# Atmega32_Dev.net
KiCad netlist of a schematic drawn in EAGLE
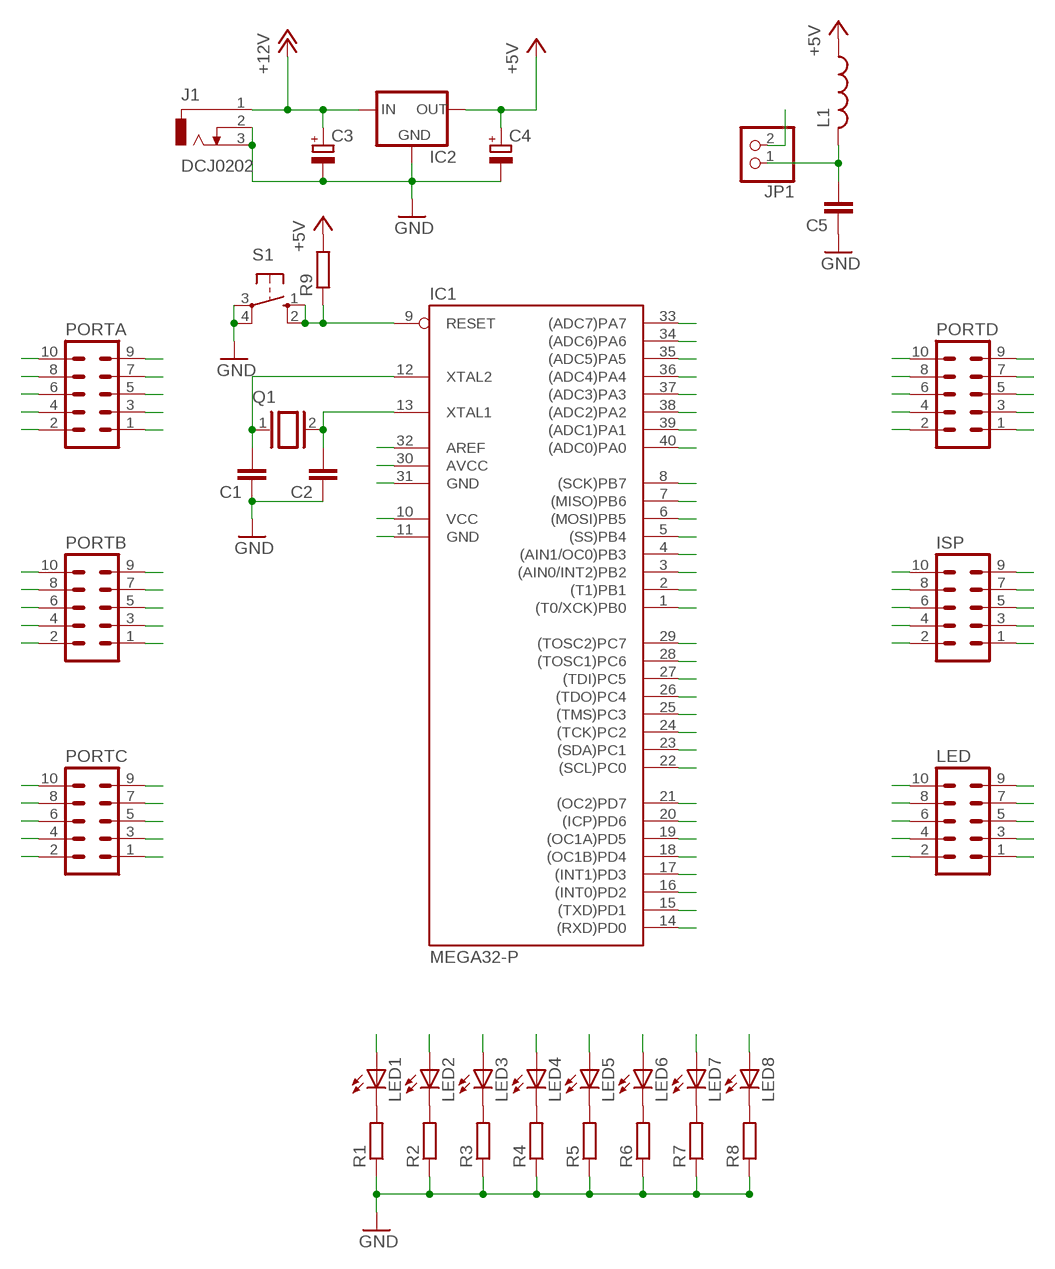
[diagram p0: schematic, sheet 1]

(export (version "E")
  (design (tool "Eeschema 10.0.6"))
  (components
    (comp (ref "C1")
      (value "CAP1206")
      (footprint "eagle-import:1206")
      (libsource (lib "eagle-import") (part "CAP1206"))
    )
    (comp (ref "C2")
      (value "CAP1206")
      (footprint "eagle-import:1206")
      (libsource (lib "eagle-import") (part "CAP1206"))
    )
    (comp (ref "C3")
      (value "CPOL-EUE5-6")
      (footprint "eagle-import:E5-6")
      (libsource (lib "eagle-import") (part "CPOL-EUE5-6"))
    )
    (comp (ref "C4")
      (value "CPOL-EUE5-6")
      (footprint "eagle-import:E5-6")
      (libsource (lib "eagle-import") (part "CPOL-EUE5-6"))
    )
    (comp (ref "C5")
      (value "CAP1206")
      (footprint "eagle-import:1206")
      (libsource (lib "eagle-import") (part "CAP1206"))
    )
    (comp (ref "IC1")
      (value "MEGA32-P")
      (footprint "eagle-import:DIL40")
      (fields (field (name "MPN") "ATMEGA32-16PU"))
      (libsource (lib "eagle-import") (part "MEGA32-P"))
    )
    (comp (ref "IC2")
      (value "78XXL")
      (footprint "eagle-import:78XXL")
      (libsource (lib "eagle-import") (part "78XXL"))
    )
    (comp (ref "ISP")
      (value "ML10")
      (footprint "eagle-import:ML10")
      (libsource (lib "eagle-import") (part "ML10"))
    )
    (comp (ref "J1")
      (value "DCJ0202")
      (footprint "eagle-import:DCJ0202")
      (libsource (lib "eagle-import") (part "DCJ0202"))
    )
    (comp (ref "JP1")
      (value "PINHD-1X2")
      (footprint "eagle-import:1X02")
      (libsource (lib "eagle-import") (part "PINHD-1X2"))
    )
    (comp (ref "L1")
      (value "L-US0204/5")
      (footprint "eagle-import:0204_5")
      (libsource (lib "eagle-import") (part "L-US0204/5"))
    )
    (comp (ref "LED")
      (value "ML10")
      (footprint "eagle-import:ML10")
      (libsource (lib "eagle-import") (part "ML10"))
    )
    (comp (ref "LED1")
      (value "LED3MM")
      (footprint "eagle-import:LED3MM")
      (libsource (lib "eagle-import") (part "LED3MM"))
    )
    (comp (ref "LED2")
      (value "LED3MM")
      (footprint "eagle-import:LED3MM")
      (libsource (lib "eagle-import") (part "LED3MM"))
    )
    (comp (ref "LED3")
      (value "LED3MM")
      (footprint "eagle-import:LED3MM")
      (libsource (lib "eagle-import") (part "LED3MM"))
    )
    (comp (ref "LED4")
      (value "LED3MM")
      (footprint "eagle-import:LED3MM")
      (libsource (lib "eagle-import") (part "LED3MM"))
    )
    (comp (ref "LED5")
      (value "LED3MM")
      (footprint "eagle-import:LED3MM")
      (libsource (lib "eagle-import") (part "LED3MM"))
    )
    (comp (ref "LED6")
      (value "LED3MM")
      (footprint "eagle-import:LED3MM")
      (libsource (lib "eagle-import") (part "LED3MM"))
    )
    (comp (ref "LED7")
      (value "LED3MM")
      (footprint "eagle-import:LED3MM")
      (libsource (lib "eagle-import") (part "LED3MM"))
    )
    (comp (ref "LED8")
      (value "LED3MM")
      (footprint "eagle-import:LED3MM")
      (libsource (lib "eagle-import") (part "LED3MM"))
    )
    (comp (ref "PORTA")
      (value "ML10")
      (footprint "eagle-import:ML10")
      (libsource (lib "eagle-import") (part "ML10"))
    )
    (comp (ref "PORTB")
      (value "ML10")
      (footprint "eagle-import:ML10")
      (libsource (lib "eagle-import") (part "ML10"))
    )
    (comp (ref "PORTC")
      (value "ML10")
      (footprint "eagle-import:ML10")
      (libsource (lib "eagle-import") (part "ML10"))
    )
    (comp (ref "PORTD")
      (value "ML10")
      (footprint "eagle-import:ML10")
      (libsource (lib "eagle-import") (part "ML10"))
    )
    (comp (ref "Q1")
      (value "XTAL/S")
      (footprint "eagle-import:QS")
      (libsource (lib "eagle-import") (part "XTAL/S"))
    )
    (comp (ref "R1")
      (value "R-EU_M1206")
      (footprint "eagle-import:M1206")
      (libsource (lib "eagle-import") (part "resistor_R-EU_M1206"))
    )
    (comp (ref "R2")
      (value "R-EU_M1206")
      (footprint "eagle-import:M1206")
      (libsource (lib "eagle-import") (part "resistor_R-EU_M1206"))
    )
    (comp (ref "R3")
      (value "R-EU_M1206")
      (footprint "eagle-import:M1206")
      (libsource (lib "eagle-import") (part "resistor_R-EU_M1206"))
    )
    (comp (ref "R4")
      (value "R-EU_M1206")
      (footprint "eagle-import:M1206")
      (libsource (lib "eagle-import") (part "resistor_R-EU_M1206"))
    )
    (comp (ref "R5")
      (value "R-EU_M1206")
      (footprint "eagle-import:M1206")
      (libsource (lib "eagle-import") (part "resistor_R-EU_M1206"))
    )
    (comp (ref "R6")
      (value "R-EU_M1206")
      (footprint "eagle-import:M1206")
      (libsource (lib "eagle-import") (part "resistor_R-EU_M1206"))
    )
    (comp (ref "R7")
      (value "R-EU_M1206")
      (footprint "eagle-import:M1206")
      (libsource (lib "eagle-import") (part "resistor_R-EU_M1206"))
    )
    (comp (ref "R8")
      (value "R-EU_M1206")
      (footprint "eagle-import:M1206")
      (libsource (lib "eagle-import") (part "resistor_R-EU_M1206"))
    )
    (comp (ref "R9")
      (value "R-EU_0204/7")
      (footprint "eagle-import:0204_7")
      (libsource (lib "eagle-import") (part "R-EU_0204/7"))
    )
    (comp (ref "S1")
      (value "10-XX")
      (footprint "eagle-import:B3F-10XX")
      (fields (field (name "MPN") "B3F-1000"))
      (libsource (lib "eagle-import") (part "10-XX"))
    )
  )
  (nets
    (net (code "1") (name "+5V") (class "Default")
      (node (ref "C4") (pin "+") (pinfunction "+_+") (pintype "passive"))
      (node (ref "IC1") (pin "10") (pinfunction "VCC_10") (pintype "power_in"))
      (node (ref "IC2") (pin "OUT") (pinfunction "OUT_OUT") (pintype "passive"))
      (node (ref "ISP") (pin "2") (pinfunction "2_2") (pintype "passive"))
      (node (ref "L1") (pin "1") (pinfunction "1_1") (pintype "passive"))
      (node (ref "LED") (pin "9") (pinfunction "9_9") (pintype "passive"))
      (node (ref "PORTA") (pin "9") (pinfunction "9_9") (pintype "passive"))
      (node (ref "PORTB") (pin "9") (pinfunction "9_9") (pintype "passive"))
      (node (ref "PORTC") (pin "9") (pinfunction "9_9") (pintype "passive"))
      (node (ref "PORTD") (pin "9") (pinfunction "9_9") (pintype "passive"))
      (node (ref "R9") (pin "2") (pinfunction "2_2") (pintype "passive"))
    )
    (net (code "2") (name "+12V") (class "Default")
      (node (ref "C3") (pin "+") (pinfunction "+_+") (pintype "passive"))
      (node (ref "IC2") (pin "IN") (pinfunction "IN_IN") (pintype "input"))
      (node (ref "J1") (pin "1") (pinfunction "1_1") (pintype "passive"))
    )
    (net (code "3") (name "/AREF") (class "Default")
      (node (ref "IC1") (pin "32") (pinfunction "AREF_32") (pintype "passive"))
      (node (ref "JP1") (pin "2") (pinfunction "2_2") (pintype "passive"))
    )
    (net (code "4") (name "/AVCC") (class "Default")
      (node (ref "C5") (pin "2") (pinfunction "2_2") (pintype "passive"))
      (node (ref "IC1") (pin "30") (pinfunction "AVCC_30") (pintype "power_in"))
      (node (ref "JP1") (pin "1") (pinfunction "1_1") (pintype "passive"))
      (node (ref "L1") (pin "2") (pinfunction "2_2") (pintype "passive"))
    )
    (net (code "5") (name "/L0") (class "Default")
      (node (ref "LED") (pin "1") (pinfunction "1_1") (pintype "passive"))
      (node (ref "LED1") (pin "A") (pinfunction "A_A") (pintype "passive"))
    )
    (net (code "6") (name "/L1") (class "Default")
      (node (ref "LED") (pin "2") (pinfunction "2_2") (pintype "passive"))
      (node (ref "LED2") (pin "A") (pinfunction "A_A") (pintype "passive"))
    )
    (net (code "7") (name "/L2") (class "Default")
      (node (ref "LED") (pin "3") (pinfunction "3_3") (pintype "passive"))
      (node (ref "LED3") (pin "A") (pinfunction "A_A") (pintype "passive"))
    )
    (net (code "8") (name "/L3") (class "Default")
      (node (ref "LED") (pin "4") (pinfunction "4_4") (pintype "passive"))
      (node (ref "LED4") (pin "A") (pinfunction "A_A") (pintype "passive"))
    )
    (net (code "9") (name "/L4") (class "Default")
      (node (ref "LED") (pin "5") (pinfunction "5_5") (pintype "passive"))
      (node (ref "LED5") (pin "A") (pinfunction "A_A") (pintype "passive"))
    )
    (net (code "10") (name "/L5") (class "Default")
      (node (ref "LED") (pin "6") (pinfunction "6_6") (pintype "passive"))
      (node (ref "LED6") (pin "A") (pinfunction "A_A") (pintype "passive"))
    )
    (net (code "11") (name "/L6") (class "Default")
      (node (ref "LED") (pin "7") (pinfunction "7_7") (pintype "passive"))
      (node (ref "LED7") (pin "A") (pinfunction "A_A") (pintype "passive"))
    )
    (net (code "12") (name "/L7") (class "Default")
      (node (ref "LED") (pin "8") (pinfunction "8_8") (pintype "passive"))
      (node (ref "LED8") (pin "A") (pinfunction "A_A") (pintype "passive"))
    )
    (net (code "13") (name "/PA0") (class "Default")
      (node (ref "IC1") (pin "40") (pinfunction "(ADC0)PA0_40") (pintype "bidirectional"))
      (node (ref "PORTA") (pin "1") (pinfunction "1_1") (pintype "passive"))
    )
    (net (code "14") (name "/PA1") (class "Default")
      (node (ref "IC1") (pin "39") (pinfunction "(ADC1)PA1_39") (pintype "bidirectional"))
      (node (ref "PORTA") (pin "2") (pinfunction "2_2") (pintype "passive"))
    )
    (net (code "15") (name "/PA2") (class "Default")
      (node (ref "IC1") (pin "38") (pinfunction "(ADC2)PA2_38") (pintype "bidirectional"))
      (node (ref "PORTA") (pin "3") (pinfunction "3_3") (pintype "passive"))
    )
    (net (code "16") (name "/PA3") (class "Default")
      (node (ref "IC1") (pin "37") (pinfunction "(ADC3)PA3_37") (pintype "bidirectional"))
      (node (ref "PORTA") (pin "4") (pinfunction "4_4") (pintype "passive"))
    )
    (net (code "17") (name "/PA4") (class "Default")
      (node (ref "IC1") (pin "36") (pinfunction "(ADC4)PA4_36") (pintype "bidirectional"))
      (node (ref "PORTA") (pin "5") (pinfunction "5_5") (pintype "passive"))
    )
    (net (code "18") (name "/PA5") (class "Default")
      (node (ref "IC1") (pin "35") (pinfunction "(ADC5)PA5_35") (pintype "bidirectional"))
      (node (ref "PORTA") (pin "6") (pinfunction "6_6") (pintype "passive"))
    )
    (net (code "19") (name "/PA6") (class "Default")
      (node (ref "IC1") (pin "34") (pinfunction "(ADC6)PA6_34") (pintype "bidirectional"))
      (node (ref "PORTA") (pin "7") (pinfunction "7_7") (pintype "passive"))
    )
    (net (code "20") (name "/PA7") (class "Default")
      (node (ref "IC1") (pin "33") (pinfunction "(ADC7)PA7_33") (pintype "bidirectional"))
      (node (ref "PORTA") (pin "8") (pinfunction "8_8") (pintype "passive"))
    )
    (net (code "21") (name "/PB0") (class "Default")
      (node (ref "IC1") (pin "1") (pinfunction "(T0/XCK)PB0_1") (pintype "bidirectional"))
      (node (ref "PORTB") (pin "1") (pinfunction "1_1") (pintype "passive"))
    )
    (net (code "22") (name "/PB1") (class "Default")
      (node (ref "IC1") (pin "2") (pinfunction "(T1)PB1_2") (pintype "bidirectional"))
      (node (ref "PORTB") (pin "2") (pinfunction "2_2") (pintype "passive"))
    )
    (net (code "23") (name "/PB2") (class "Default")
      (node (ref "IC1") (pin "3") (pinfunction "(AIN0/INT2)PB2_3") (pintype "bidirectional"))
      (node (ref "PORTB") (pin "3") (pinfunction "3_3") (pintype "passive"))
    )
    (net (code "24") (name "/PB3") (class "Default")
      (node (ref "IC1") (pin "4") (pinfunction "(AIN1/OC0)PB3_4") (pintype "bidirectional"))
      (node (ref "PORTB") (pin "4") (pinfunction "4_4") (pintype "passive"))
    )
    (net (code "25") (name "/PB4") (class "Default")
      (node (ref "IC1") (pin "5") (pinfunction "(SS)PB4_5") (pintype "bidirectional"))
      (node (ref "PORTB") (pin "5") (pinfunction "5_5") (pintype "passive"))
    )
    (net (code "26") (name "/PB5") (class "Default")
      (node (ref "IC1") (pin "6") (pinfunction "(MOSI)PB5_6") (pintype "bidirectional"))
      (node (ref "ISP") (pin "9") (pinfunction "9_9") (pintype "passive"))
      (node (ref "PORTB") (pin "6") (pinfunction "6_6") (pintype "passive"))
    )
    (net (code "27") (name "/PB6") (class "Default")
      (node (ref "IC1") (pin "7") (pinfunction "(MISO)PB6_7") (pintype "bidirectional"))
      (node (ref "ISP") (pin "1") (pinfunction "1_1") (pintype "passive"))
      (node (ref "PORTB") (pin "7") (pinfunction "7_7") (pintype "passive"))
    )
    (net (code "28") (name "/PB7") (class "Default")
      (node (ref "IC1") (pin "8") (pinfunction "(SCK)PB7_8") (pintype "bidirectional"))
      (node (ref "ISP") (pin "7") (pinfunction "7_7") (pintype "passive"))
      (node (ref "PORTB") (pin "8") (pinfunction "8_8") (pintype "passive"))
    )
    (net (code "29") (name "/PC0") (class "Default")
      (node (ref "IC1") (pin "22") (pinfunction "(SCL)PC0_22") (pintype "bidirectional"))
      (node (ref "PORTC") (pin "1") (pinfunction "1_1") (pintype "passive"))
    )
    (net (code "30") (name "/PC1") (class "Default")
      (node (ref "IC1") (pin "23") (pinfunction "(SDA)PC1_23") (pintype "bidirectional"))
      (node (ref "PORTC") (pin "2") (pinfunction "2_2") (pintype "passive"))
    )
    (net (code "31") (name "/PC2") (class "Default")
      (node (ref "IC1") (pin "24") (pinfunction "(TCK)PC2_24") (pintype "bidirectional"))
      (node (ref "PORTC") (pin "3") (pinfunction "3_3") (pintype "passive"))
    )
    (net (code "32") (name "/PC3") (class "Default")
      (node (ref "IC1") (pin "25") (pinfunction "(TMS)PC3_25") (pintype "bidirectional"))
      (node (ref "PORTC") (pin "4") (pinfunction "4_4") (pintype "passive"))
    )
    (net (code "33") (name "/PC4") (class "Default")
      (node (ref "IC1") (pin "26") (pinfunction "(TDO)PC4_26") (pintype "bidirectional"))
      (node (ref "PORTC") (pin "5") (pinfunction "5_5") (pintype "passive"))
    )
    (net (code "34") (name "/PC5") (class "Default")
      (node (ref "IC1") (pin "27") (pinfunction "(TDI)PC5_27") (pintype "bidirectional"))
      (node (ref "PORTC") (pin "6") (pinfunction "6_6") (pintype "passive"))
    )
    (net (code "35") (name "/PC6") (class "Default")
      (node (ref "IC1") (pin "28") (pinfunction "(TOSC1)PC6_28") (pintype "bidirectional"))
      (node (ref "PORTC") (pin "7") (pinfunction "7_7") (pintype "passive"))
    )
    (net (code "36") (name "/PC7") (class "Default")
      (node (ref "IC1") (pin "29") (pinfunction "(TOSC2)PC7_29") (pintype "bidirectional"))
      (node (ref "PORTC") (pin "8") (pinfunction "8_8") (pintype "passive"))
    )
    (net (code "37") (name "/PD0") (class "Default")
      (node (ref "IC1") (pin "14") (pinfunction "(RXD)PD0_14") (pintype "bidirectional"))
      (node (ref "PORTD") (pin "1") (pinfunction "1_1") (pintype "passive"))
    )
    (net (code "38") (name "/PD1") (class "Default")
      (node (ref "IC1") (pin "15") (pinfunction "(TXD)PD1_15") (pintype "bidirectional"))
      (node (ref "PORTD") (pin "2") (pinfunction "2_2") (pintype "passive"))
    )
    (net (code "39") (name "/PD2") (class "Default")
      (node (ref "IC1") (pin "16") (pinfunction "(INT0)PD2_16") (pintype "bidirectional"))
      (node (ref "PORTD") (pin "3") (pinfunction "3_3") (pintype "passive"))
    )
    (net (code "40") (name "/PD3") (class "Default")
      (node (ref "IC1") (pin "17") (pinfunction "(INT1)PD3_17") (pintype "bidirectional"))
      (node (ref "PORTD") (pin "4") (pinfunction "4_4") (pintype "passive"))
    )
    (net (code "41") (name "/PD4") (class "Default")
      (node (ref "IC1") (pin "18") (pinfunction "(OC1B)PD4_18") (pintype "bidirectional"))
      (node (ref "PORTD") (pin "5") (pinfunction "5_5") (pintype "passive"))
    )
    (net (code "42") (name "/PD5") (class "Default")
      (node (ref "IC1") (pin "19") (pinfunction "(OC1A)PD5_19") (pintype "bidirectional"))
      (node (ref "PORTD") (pin "6") (pinfunction "6_6") (pintype "passive"))
    )
    (net (code "43") (name "/PD6") (class "Default")
      (node (ref "IC1") (pin "20") (pinfunction "(ICP)PD6_20") (pintype "bidirectional"))
      (node (ref "PORTD") (pin "7") (pinfunction "7_7") (pintype "passive"))
    )
    (net (code "44") (name "/PD7") (class "Default")
      (node (ref "IC1") (pin "21") (pinfunction "(OC2)PD7_21") (pintype "bidirectional"))
      (node (ref "PORTD") (pin "8") (pinfunction "8_8") (pintype "passive"))
    )
    (net (code "45") (name "/RESET") (class "Default")
      (node (ref "IC1") (pin "9") (pinfunction "RESET_9") (pintype "input"))
      (node (ref "ISP") (pin "5") (pinfunction "5_5") (pintype "passive"))
      (node (ref "R9") (pin "1") (pinfunction "1_1") (pintype "passive"))
      (node (ref "S1") (pin "1") (pinfunction "S_1") (pintype "passive"))
      (node (ref "S1") (pin "2") (pinfunction "S1_2") (pintype "passive"))
    )
    (net (code "46") (name "GND") (class "Default")
      (node (ref "C1") (pin "1") (pinfunction "1_1") (pintype "passive"))
      (node (ref "C2") (pin "1") (pinfunction "1_1") (pintype "passive"))
      (node (ref "C3") (pin "-") (pinfunction "-_-") (pintype "passive"))
      (node (ref "C4") (pin "-") (pinfunction "-_-") (pintype "passive"))
      (node (ref "C5") (pin "1") (pinfunction "1_1") (pintype "passive"))
      (node (ref "IC1") (pin "11") (pinfunction "GND_11") (pintype "power_in"))
      (node (ref "IC1") (pin "31") (pinfunction "GND_31") (pintype "power_in"))
      (node (ref "IC2") (pin "GND") (pinfunction "GND_GND") (pintype "input"))
      (node (ref "ISP") (pin "10") (pinfunction "10_10") (pintype "passive"))
      (node (ref "ISP") (pin "4") (pinfunction "4_4") (pintype "passive"))
      (node (ref "ISP") (pin "6") (pinfunction "6_6") (pintype "passive"))
      (node (ref "ISP") (pin "8") (pinfunction "8_8") (pintype "passive"))
      (node (ref "J1") (pin "2") (pinfunction "2_2") (pintype "passive"))
      (node (ref "J1") (pin "3") (pinfunction "3_3") (pintype "passive"))
      (node (ref "LED") (pin "10") (pinfunction "10_10") (pintype "passive"))
      (node (ref "PORTA") (pin "10") (pinfunction "10_10") (pintype "passive"))
      (node (ref "PORTB") (pin "10") (pinfunction "10_10") (pintype "passive"))
      (node (ref "PORTC") (pin "10") (pinfunction "10_10") (pintype "passive"))
      (node (ref "PORTD") (pin "10") (pinfunction "10_10") (pintype "passive"))
      (node (ref "R1") (pin "1") (pinfunction "1_1") (pintype "passive"))
      (node (ref "R2") (pin "1") (pinfunction "1_1") (pintype "passive"))
      (node (ref "R3") (pin "1") (pinfunction "1_1") (pintype "passive"))
      (node (ref "R4") (pin "1") (pinfunction "1_1") (pintype "passive"))
      (node (ref "R5") (pin "1") (pinfunction "1_1") (pintype "passive"))
      (node (ref "R6") (pin "1") (pinfunction "1_1") (pintype "passive"))
      (node (ref "R7") (pin "1") (pinfunction "1_1") (pintype "passive"))
      (node (ref "R8") (pin "1") (pinfunction "1_1") (pintype "passive"))
      (node (ref "S1") (pin "3") (pinfunction "P_3") (pintype "passive"))
      (node (ref "S1") (pin "4") (pinfunction "P1_4") (pintype "passive"))
    )
    (net (code "47") (name "Net-(IC1-XTAL1)") (class "Default")
      (node (ref "C2") (pin "2") (pinfunction "2_2") (pintype "passive"))
      (node (ref "IC1") (pin "13") (pinfunction "XTAL1_13") (pintype "bidirectional"))
      (node (ref "Q1") (pin "2") (pinfunction "2_2") (pintype "passive"))
    )
    (net (code "48") (name "Net-(IC1-XTAL2)") (class "Default")
      (node (ref "C1") (pin "2") (pinfunction "2_2") (pintype "passive"))
      (node (ref "IC1") (pin "12") (pinfunction "XTAL2_12") (pintype "bidirectional"))
      (node (ref "Q1") (pin "1") (pinfunction "1_1") (pintype "passive"))
    )
    (net (code "49") (name "Net-(LED1-C)") (class "Default")
      (node (ref "LED1") (pin "K") (pinfunction "C_K") (pintype "passive"))
      (node (ref "R1") (pin "2") (pinfunction "2_2") (pintype "passive"))
    )
    (net (code "50") (name "Net-(LED2-C)") (class "Default")
      (node (ref "LED2") (pin "K") (pinfunction "C_K") (pintype "passive"))
      (node (ref "R2") (pin "2") (pinfunction "2_2") (pintype "passive"))
    )
    (net (code "51") (name "Net-(LED3-C)") (class "Default")
      (node (ref "LED3") (pin "K") (pinfunction "C_K") (pintype "passive"))
      (node (ref "R3") (pin "2") (pinfunction "2_2") (pintype "passive"))
    )
    (net (code "52") (name "Net-(LED4-C)") (class "Default")
      (node (ref "LED4") (pin "K") (pinfunction "C_K") (pintype "passive"))
      (node (ref "R4") (pin "2") (pinfunction "2_2") (pintype "passive"))
    )
    (net (code "53") (name "Net-(LED5-C)") (class "Default")
      (node (ref "LED5") (pin "K") (pinfunction "C_K") (pintype "passive"))
      (node (ref "R5") (pin "2") (pinfunction "2_2") (pintype "passive"))
    )
    (net (code "54") (name "Net-(LED6-C)") (class "Default")
      (node (ref "LED6") (pin "K") (pinfunction "C_K") (pintype "passive"))
      (node (ref "R6") (pin "2") (pinfunction "2_2") (pintype "passive"))
    )
    (net (code "55") (name "Net-(LED7-C)") (class "Default")
      (node (ref "LED7") (pin "K") (pinfunction "C_K") (pintype "passive"))
      (node (ref "R7") (pin "2") (pinfunction "2_2") (pintype "passive"))
    )
    (net (code "56") (name "Net-(LED8-C)") (class "Default")
      (node (ref "LED8") (pin "K") (pinfunction "C_K") (pintype "passive"))
      (node (ref "R8") (pin "2") (pinfunction "2_2") (pintype "passive"))
    )
    (net (code "57") (name "unconnected-(ISP-Pad3)") (class "Default")
      (node (ref "ISP") (pin "3") (pinfunction "3_3") (pintype "passive"))
    )
  )
)
